# Temperature_Sensor.net
KiCad netlist of a schematic drawn in Altium Designer
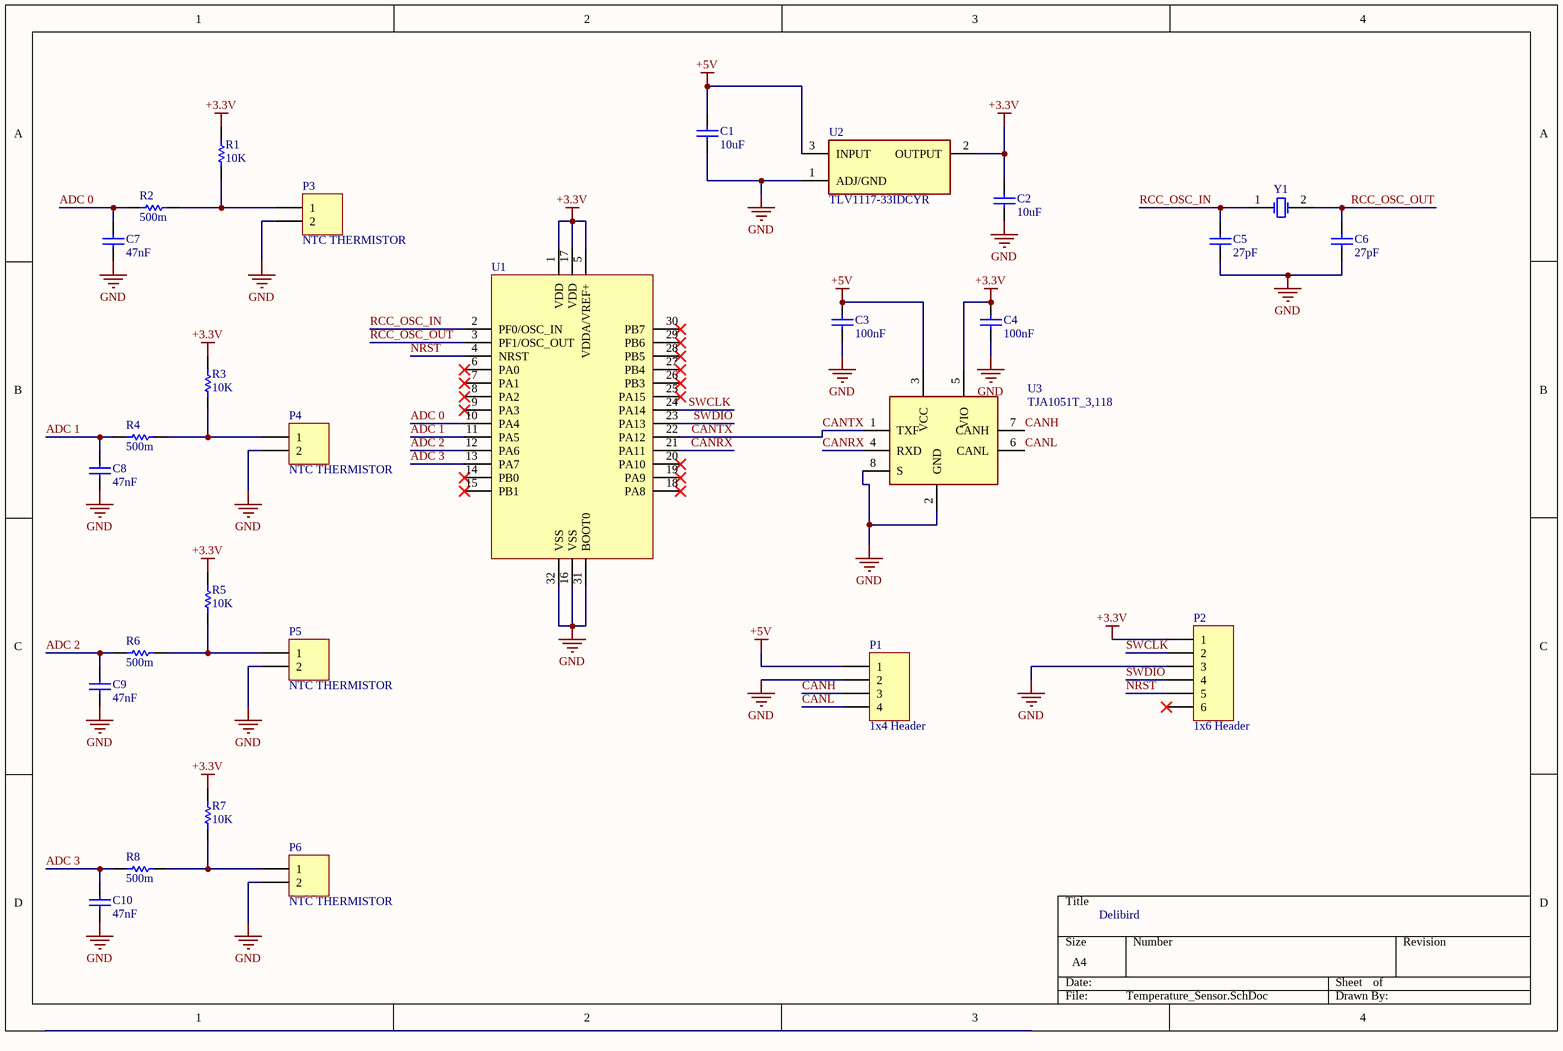
[diagram p0: Temperature_Sensor.SchDoc]

(export (version "E")
  (design (tool "Eeschema 10.0.6"))
  (components
    (comp (ref "C1")
      (value "10uF")
      (footprint "0805 - Capacitor")
      (description "Nonpolarized Capacitor")
      (fields (field (name "Comment") "Capacitor - Nonpolarized"))
      (libsource (lib "General") (part "Capacitor - Nonpolarized"))
    )
    (comp (ref "C2")
      (value "10uF")
      (footprint "0805 - Capacitor")
      (description "Nonpolarized Capacitor")
      (fields (field (name "Comment") "Capacitor - Nonpolarized"))
      (libsource (lib "General") (part "Capacitor - Nonpolarized"))
    )
    (comp (ref "C3")
      (value "100nF")
      (footprint "0805 - Capacitor")
      (description "Nonpolarized Capacitor")
      (fields (field (name "Comment") "Capacitor - Nonpolarized"))
      (libsource (lib "General") (part "Capacitor - Nonpolarized"))
    )
    (comp (ref "C4")
      (value "100nF")
      (footprint "0805 - Capacitor")
      (description "Nonpolarized Capacitor")
      (fields (field (name "Comment") "Capacitor - Nonpolarized"))
      (libsource (lib "General") (part "Capacitor - Nonpolarized"))
    )
    (comp (ref "C5")
      (value "27pF")
      (footprint "0805 - Capacitor")
      (description "Nonpolarized Capacitor")
      (fields (field (name "Comment") "Capacitor - Nonpolarized"))
      (libsource (lib "General") (part "Capacitor - Nonpolarized"))
    )
    (comp (ref "C6")
      (value "27pF")
      (footprint "0805 - Capacitor")
      (description "Nonpolarized Capacitor")
      (fields (field (name "Comment") "Capacitor - Nonpolarized"))
      (libsource (lib "General") (part "Capacitor - Nonpolarized"))
    )
    (comp (ref "C7")
      (value "47nF")
      (footprint "0805 - Capacitor")
      (description "Nonpolarized Capacitor")
      (fields (field (name "Comment") "Capacitor - Nonpolarized"))
      (libsource (lib "General") (part "Capacitor - Nonpolarized"))
    )
    (comp (ref "C8")
      (value "47nF")
      (footprint "0805 - Capacitor")
      (description "Nonpolarized Capacitor")
      (fields (field (name "Comment") "Capacitor - Nonpolarized"))
      (libsource (lib "General") (part "Capacitor - Nonpolarized"))
    )
    (comp (ref "C9")
      (value "47nF")
      (footprint "0805 - Capacitor")
      (description "Nonpolarized Capacitor")
      (fields (field (name "Comment") "Capacitor - Nonpolarized"))
      (libsource (lib "General") (part "Capacitor - Nonpolarized"))
    )
    (comp (ref "C10")
      (value "47nF")
      (footprint "0805 - Capacitor")
      (description "Nonpolarized Capacitor")
      (fields (field (name "Comment") "Capacitor - Nonpolarized"))
      (libsource (lib "General") (part "Capacitor - Nonpolarized"))
    )
    (comp (ref "P1")
      (value "1x4 Header")
      (footprint "HDR1X4")
      (description "1x4 Pin Header")
      (libsource (lib "GeneralConnectors") (part "1x4 Header"))
    )
    (comp (ref "P2")
      (value "1x6 Header")
      (footprint "HDR1X6")
      (description "1x6 Pin Header")
      (libsource (lib "GeneralConnectors") (part "1x6 Header"))
    )
    (comp (ref "P3")
      (value "NTC THERMISTOR")
      (footprint "HDR1X2")
      (description "1x2 Pin Header")
      (libsource (lib "GeneralConnectors") (part "1x2 Header"))
    )
    (comp (ref "P4")
      (value "NTC THERMISTOR")
      (footprint "HDR1X2")
      (description "1x2 Pin Header")
      (libsource (lib "GeneralConnectors") (part "1x2 Header"))
    )
    (comp (ref "P5")
      (value "NTC THERMISTOR")
      (footprint "HDR1X2")
      (description "1x2 Pin Header")
      (libsource (lib "GeneralConnectors") (part "1x2 Header"))
    )
    (comp (ref "P6")
      (value "NTC THERMISTOR")
      (footprint "HDR1X2")
      (description "1x2 Pin Header")
      (libsource (lib "GeneralConnectors") (part "1x2 Header"))
    )
    (comp (ref "R1")
      (value "10K")
      (footprint "0603 - Resistor")
      (description "Resistor")
      (libsource (lib "General") (part "Resistor"))
    )
    (comp (ref "R2")
      (value "500m")
      (footprint "0603 - Resistor")
      (description "Resistor")
      (libsource (lib "General") (part "Resistor"))
    )
    (comp (ref "R3")
      (value "10K")
      (footprint "0603 - Resistor")
      (description "Resistor")
      (libsource (lib "General") (part "Resistor"))
    )
    (comp (ref "R4")
      (value "500m")
      (footprint "0603 - Resistor")
      (description "Resistor")
      (libsource (lib "General") (part "Resistor"))
    )
    (comp (ref "R5")
      (value "10K")
      (footprint "0603 - Resistor")
      (description "Resistor")
      (libsource (lib "General") (part "Resistor"))
    )
    (comp (ref "R6")
      (value "500m")
      (footprint "0603 - Resistor")
      (description "Resistor")
      (libsource (lib "General") (part "Resistor"))
    )
    (comp (ref "R7")
      (value "10K")
      (footprint "0603 - Resistor")
      (description "Resistor")
      (libsource (lib "General") (part "Resistor"))
    )
    (comp (ref "R8")
      (value "500m")
      (footprint "0603 - Resistor")
      (description "Resistor")
      (libsource (lib "General") (part "Resistor"))
    )
    (comp (ref "U1")
      (value "STM32F303K6T6")
      (footprint "QFP80P900X900X160-32N")
      (description "Integrated Circuit")
      (libsource (lib "Embedded") (part "STM32F303K6T6"))
    )
    (comp (ref "U2")
      (value "TLV1117-33IDCYR")
      (footprint "TLV1117")
      (description "Linear Voltage Regulator IC 3.3V 800MA SOT223-4")
      (fields (field (name "MANUFACTURER") "Texas Instruments"))
      (libsource (lib "GeneralComponents") (part "TLV1117-33IDCYR"))
    )
    (comp (ref "U3")
      (value "TJA1051T_3,118")
      (footprint "TJA1051T/3,118")
      (description "CAN Transceiver IC 4.5V-5.5V 250ns")
      (fields (field (name "MANUFACTURER") "NXP") (field (name "MANUFACTURER PART NUMBER") "TJA1051T/3,118"))
      (libsource (lib "GeneralComponents") (part "TJA1051T_3,118"))
    )
    (comp (ref "Y1")
      (value "Oscillator")
      (footprint "2-SMD NO LEAD CRSYSTAL")
      (description "Crystal Oscillator")
      (libsource (lib "General") (part "Oscillator"))
    )
  )
  (nets
    (net (code "1") (name "+3.3V") (class "Default")
      (node (ref "C2") (pin "2") (pinfunction "2_2") (pintype "passive"))
      (node (ref "C4") (pin "2") (pinfunction "2_2") (pintype "passive"))
      (node (ref "P2") (pin "1") (pinfunction "1_1") (pintype "passive"))
      (node (ref "R1") (pin "2") (pinfunction "2_2") (pintype "passive"))
      (node (ref "R3") (pin "2") (pinfunction "2_2") (pintype "passive"))
      (node (ref "R5") (pin "2") (pinfunction "2_2") (pintype "passive"))
      (node (ref "R7") (pin "2") (pinfunction "2_2") (pintype "passive"))
      (node (ref "U1") (pin "1") (pinfunction "VDD_1") (pintype "passive"))
      (node (ref "U1") (pin "17") (pinfunction "VDD_17") (pintype "passive"))
      (node (ref "U1") (pin "5") (pinfunction "VDDA/VREF+_5") (pintype "passive"))
      (node (ref "U2") (pin "2") (pinfunction "OUTPUT_2") (pintype "passive"))
      (node (ref "U3") (pin "5") (pinfunction "VIO_5") (pintype "passive"))
    )
    (net (code "2") (name "+5V") (class "Default")
      (node (ref "C1") (pin "2") (pinfunction "2_2") (pintype "passive"))
      (node (ref "C3") (pin "2") (pinfunction "2_2") (pintype "passive"))
      (node (ref "P1") (pin "1") (pinfunction "1_1") (pintype "passive"))
      (node (ref "U2") (pin "3") (pinfunction "INPUT_3") (pintype "passive"))
      (node (ref "U3") (pin "3") (pinfunction "VCC_3") (pintype "passive"))
    )
    (net (code "3") (name "/ADC 0") (class "Default")
      (node (ref "C7") (pin "2") (pinfunction "2_2") (pintype "passive"))
      (node (ref "R2") (pin "2") (pinfunction "2_2") (pintype "passive"))
      (node (ref "U1") (pin "10") (pinfunction "PA4_10") (pintype "passive"))
    )
    (net (code "4") (name "/ADC 1") (class "Default")
      (node (ref "C8") (pin "2") (pinfunction "2_2") (pintype "passive"))
      (node (ref "R4") (pin "2") (pinfunction "2_2") (pintype "passive"))
      (node (ref "U1") (pin "11") (pinfunction "PA5_11") (pintype "passive"))
    )
    (net (code "5") (name "/ADC 2") (class "Default")
      (node (ref "C9") (pin "2") (pinfunction "2_2") (pintype "passive"))
      (node (ref "R6") (pin "2") (pinfunction "2_2") (pintype "passive"))
      (node (ref "U1") (pin "12") (pinfunction "PA6_12") (pintype "passive"))
    )
    (net (code "6") (name "/ADC 3") (class "Default")
      (node (ref "C10") (pin "2") (pinfunction "2_2") (pintype "passive"))
      (node (ref "R8") (pin "2") (pinfunction "2_2") (pintype "passive"))
      (node (ref "U1") (pin "13") (pinfunction "PA7_13") (pintype "passive"))
    )
    (net (code "7") (name "/CANH") (class "Default")
      (node (ref "P1") (pin "3") (pinfunction "3_3") (pintype "passive"))
      (node (ref "U3") (pin "7") (pinfunction "CANH_7") (pintype "passive"))
    )
    (net (code "8") (name "/CANL") (class "Default")
      (node (ref "P1") (pin "4") (pinfunction "4_4") (pintype "passive"))
      (node (ref "U3") (pin "6") (pinfunction "CANL_6") (pintype "passive"))
    )
    (net (code "9") (name "/CANRX") (class "Default")
      (node (ref "U1") (pin "21") (pinfunction "PA11_21") (pintype "passive"))
      (node (ref "U3") (pin "4") (pinfunction "RXD_4") (pintype "passive"))
    )
    (net (code "10") (name "/CANTX") (class "Default")
      (node (ref "U1") (pin "22") (pinfunction "PA12_22") (pintype "passive"))
      (node (ref "U3") (pin "1") (pinfunction "TXF_1") (pintype "passive"))
    )
    (net (code "11") (name "/NRST") (class "Default")
      (node (ref "P2") (pin "5") (pinfunction "5_5") (pintype "passive"))
      (node (ref "U1") (pin "4") (pinfunction "NRST_4") (pintype "passive"))
    )
    (net (code "12") (name "/RCC_OSC_IN") (class "Default")
      (node (ref "C5") (pin "1") (pinfunction "1_1") (pintype "passive"))
      (node (ref "U1") (pin "2") (pinfunction "PF0/OSC_IN_2") (pintype "passive"))
      (node (ref "Y1") (pin "1") (pinfunction "OSC1_1") (pintype "passive"))
    )
    (net (code "13") (name "/RCC_OSC_OUT") (class "Default")
      (node (ref "C6") (pin "1") (pinfunction "1_1") (pintype "passive"))
      (node (ref "U1") (pin "3") (pinfunction "PF1/OSC_OUT_3") (pintype "passive"))
      (node (ref "Y1") (pin "2") (pinfunction "OSC2_2") (pintype "passive"))
    )
    (net (code "14") (name "/SWCLK") (class "Default")
      (node (ref "P2") (pin "2") (pinfunction "2_2") (pintype "passive"))
      (node (ref "U1") (pin "24") (pinfunction "PA14_24") (pintype "passive"))
    )
    (net (code "15") (name "/SWDIO") (class "Default")
      (node (ref "P2") (pin "4") (pinfunction "4_4") (pintype "passive"))
      (node (ref "U1") (pin "23") (pinfunction "PA13_23") (pintype "passive"))
    )
    (net (code "16") (name "GND") (class "Default")
      (node (ref "C1") (pin "1") (pinfunction "1_1") (pintype "passive"))
      (node (ref "C10") (pin "1") (pinfunction "1_1") (pintype "passive"))
      (node (ref "C2") (pin "1") (pinfunction "1_1") (pintype "passive"))
      (node (ref "C3") (pin "1") (pinfunction "1_1") (pintype "passive"))
      (node (ref "C4") (pin "1") (pinfunction "1_1") (pintype "passive"))
      (node (ref "C5") (pin "2") (pinfunction "2_2") (pintype "passive"))
      (node (ref "C6") (pin "2") (pinfunction "2_2") (pintype "passive"))
      (node (ref "C7") (pin "1") (pinfunction "1_1") (pintype "passive"))
      (node (ref "C8") (pin "1") (pinfunction "1_1") (pintype "passive"))
      (node (ref "C9") (pin "1") (pinfunction "1_1") (pintype "passive"))
      (node (ref "P1") (pin "2") (pinfunction "2_2") (pintype "passive"))
      (node (ref "P2") (pin "3") (pinfunction "3_3") (pintype "passive"))
      (node (ref "P3") (pin "2") (pinfunction "2_2") (pintype "passive"))
      (node (ref "P4") (pin "2") (pinfunction "2_2") (pintype "passive"))
      (node (ref "P5") (pin "2") (pinfunction "2_2") (pintype "passive"))
      (node (ref "P6") (pin "2") (pinfunction "2_2") (pintype "passive"))
      (node (ref "U1") (pin "16") (pinfunction "VSS_16") (pintype "passive"))
      (node (ref "U1") (pin "31") (pinfunction "BOOT0_31") (pintype "passive"))
      (node (ref "U1") (pin "32") (pinfunction "VSS_32") (pintype "passive"))
      (node (ref "U2") (pin "1") (pinfunction "ADJ/GND_1") (pintype "passive"))
      (node (ref "U3") (pin "2") (pinfunction "GND_2") (pintype "passive"))
      (node (ref "U3") (pin "8") (pinfunction "S_8") (pintype "passive"))
    )
    (net (code "17") (name "Net-(P3-Pad1)") (class "Default")
      (node (ref "P3") (pin "1") (pinfunction "1_1") (pintype "passive"))
      (node (ref "R1") (pin "1") (pinfunction "1_1") (pintype "passive"))
      (node (ref "R2") (pin "1") (pinfunction "1_1") (pintype "passive"))
    )
    (net (code "18") (name "Net-(P4-Pad1)") (class "Default")
      (node (ref "P4") (pin "1") (pinfunction "1_1") (pintype "passive"))
      (node (ref "R3") (pin "1") (pinfunction "1_1") (pintype "passive"))
      (node (ref "R4") (pin "1") (pinfunction "1_1") (pintype "passive"))
    )
    (net (code "19") (name "Net-(P5-Pad1)") (class "Default")
      (node (ref "P5") (pin "1") (pinfunction "1_1") (pintype "passive"))
      (node (ref "R5") (pin "1") (pinfunction "1_1") (pintype "passive"))
      (node (ref "R6") (pin "1") (pinfunction "1_1") (pintype "passive"))
    )
    (net (code "20") (name "Net-(P6-Pad1)") (class "Default")
      (node (ref "P6") (pin "1") (pinfunction "1_1") (pintype "passive"))
      (node (ref "R7") (pin "1") (pinfunction "1_1") (pintype "passive"))
      (node (ref "R8") (pin "1") (pinfunction "1_1") (pintype "passive"))
    )
    (net (code "21") (name "unconnected-(P2-Pad6)") (class "Default")
      (node (ref "P2") (pin "6") (pinfunction "6_6") (pintype "passive+no_connect"))
    )
    (net (code "22") (name "unconnected-(U1-PA0-Pad6)") (class "Default")
      (node (ref "U1") (pin "6") (pinfunction "PA0_6") (pintype "passive+no_connect"))
    )
    (net (code "23") (name "unconnected-(U1-PA1-Pad7)") (class "Default")
      (node (ref "U1") (pin "7") (pinfunction "PA1_7") (pintype "passive+no_connect"))
    )
    (net (code "24") (name "unconnected-(U1-PA2-Pad8)") (class "Default")
      (node (ref "U1") (pin "8") (pinfunction "PA2_8") (pintype "passive+no_connect"))
    )
    (net (code "25") (name "unconnected-(U1-PA3-Pad9)") (class "Default")
      (node (ref "U1") (pin "9") (pinfunction "PA3_9") (pintype "passive+no_connect"))
    )
    (net (code "26") (name "unconnected-(U1-PA8-Pad18)") (class "Default")
      (node (ref "U1") (pin "18") (pinfunction "PA8_18") (pintype "passive+no_connect"))
    )
    (net (code "27") (name "unconnected-(U1-PA9-Pad19)") (class "Default")
      (node (ref "U1") (pin "19") (pinfunction "PA9_19") (pintype "passive+no_connect"))
    )
    (net (code "28") (name "unconnected-(U1-PA10-Pad20)") (class "Default")
      (node (ref "U1") (pin "20") (pinfunction "PA10_20") (pintype "passive+no_connect"))
    )
    (net (code "29") (name "unconnected-(U1-PA15-Pad25)") (class "Default")
      (node (ref "U1") (pin "25") (pinfunction "PA15_25") (pintype "passive+no_connect"))
    )
    (net (code "30") (name "unconnected-(U1-PB0-Pad14)") (class "Default")
      (node (ref "U1") (pin "14") (pinfunction "PB0_14") (pintype "passive+no_connect"))
    )
    (net (code "31") (name "unconnected-(U1-PB1-Pad15)") (class "Default")
      (node (ref "U1") (pin "15") (pinfunction "PB1_15") (pintype "passive+no_connect"))
    )
    (net (code "32") (name "unconnected-(U1-PB3-Pad26)") (class "Default")
      (node (ref "U1") (pin "26") (pinfunction "PB3_26") (pintype "passive+no_connect"))
    )
    (net (code "33") (name "unconnected-(U1-PB4-Pad27)") (class "Default")
      (node (ref "U1") (pin "27") (pinfunction "PB4_27") (pintype "passive+no_connect"))
    )
    (net (code "34") (name "unconnected-(U1-PB5-Pad28)") (class "Default")
      (node (ref "U1") (pin "28") (pinfunction "PB5_28") (pintype "passive+no_connect"))
    )
    (net (code "35") (name "unconnected-(U1-PB6-Pad29)") (class "Default")
      (node (ref "U1") (pin "29") (pinfunction "PB6_29") (pintype "passive+no_connect"))
    )
    (net (code "36") (name "unconnected-(U1-PB7-Pad30)") (class "Default")
      (node (ref "U1") (pin "30") (pinfunction "PB7_30") (pintype "passive+no_connect"))
    )
  )
)
